# gimli1_1.net
KiCad netlist of a schematic drawn in EAGLE
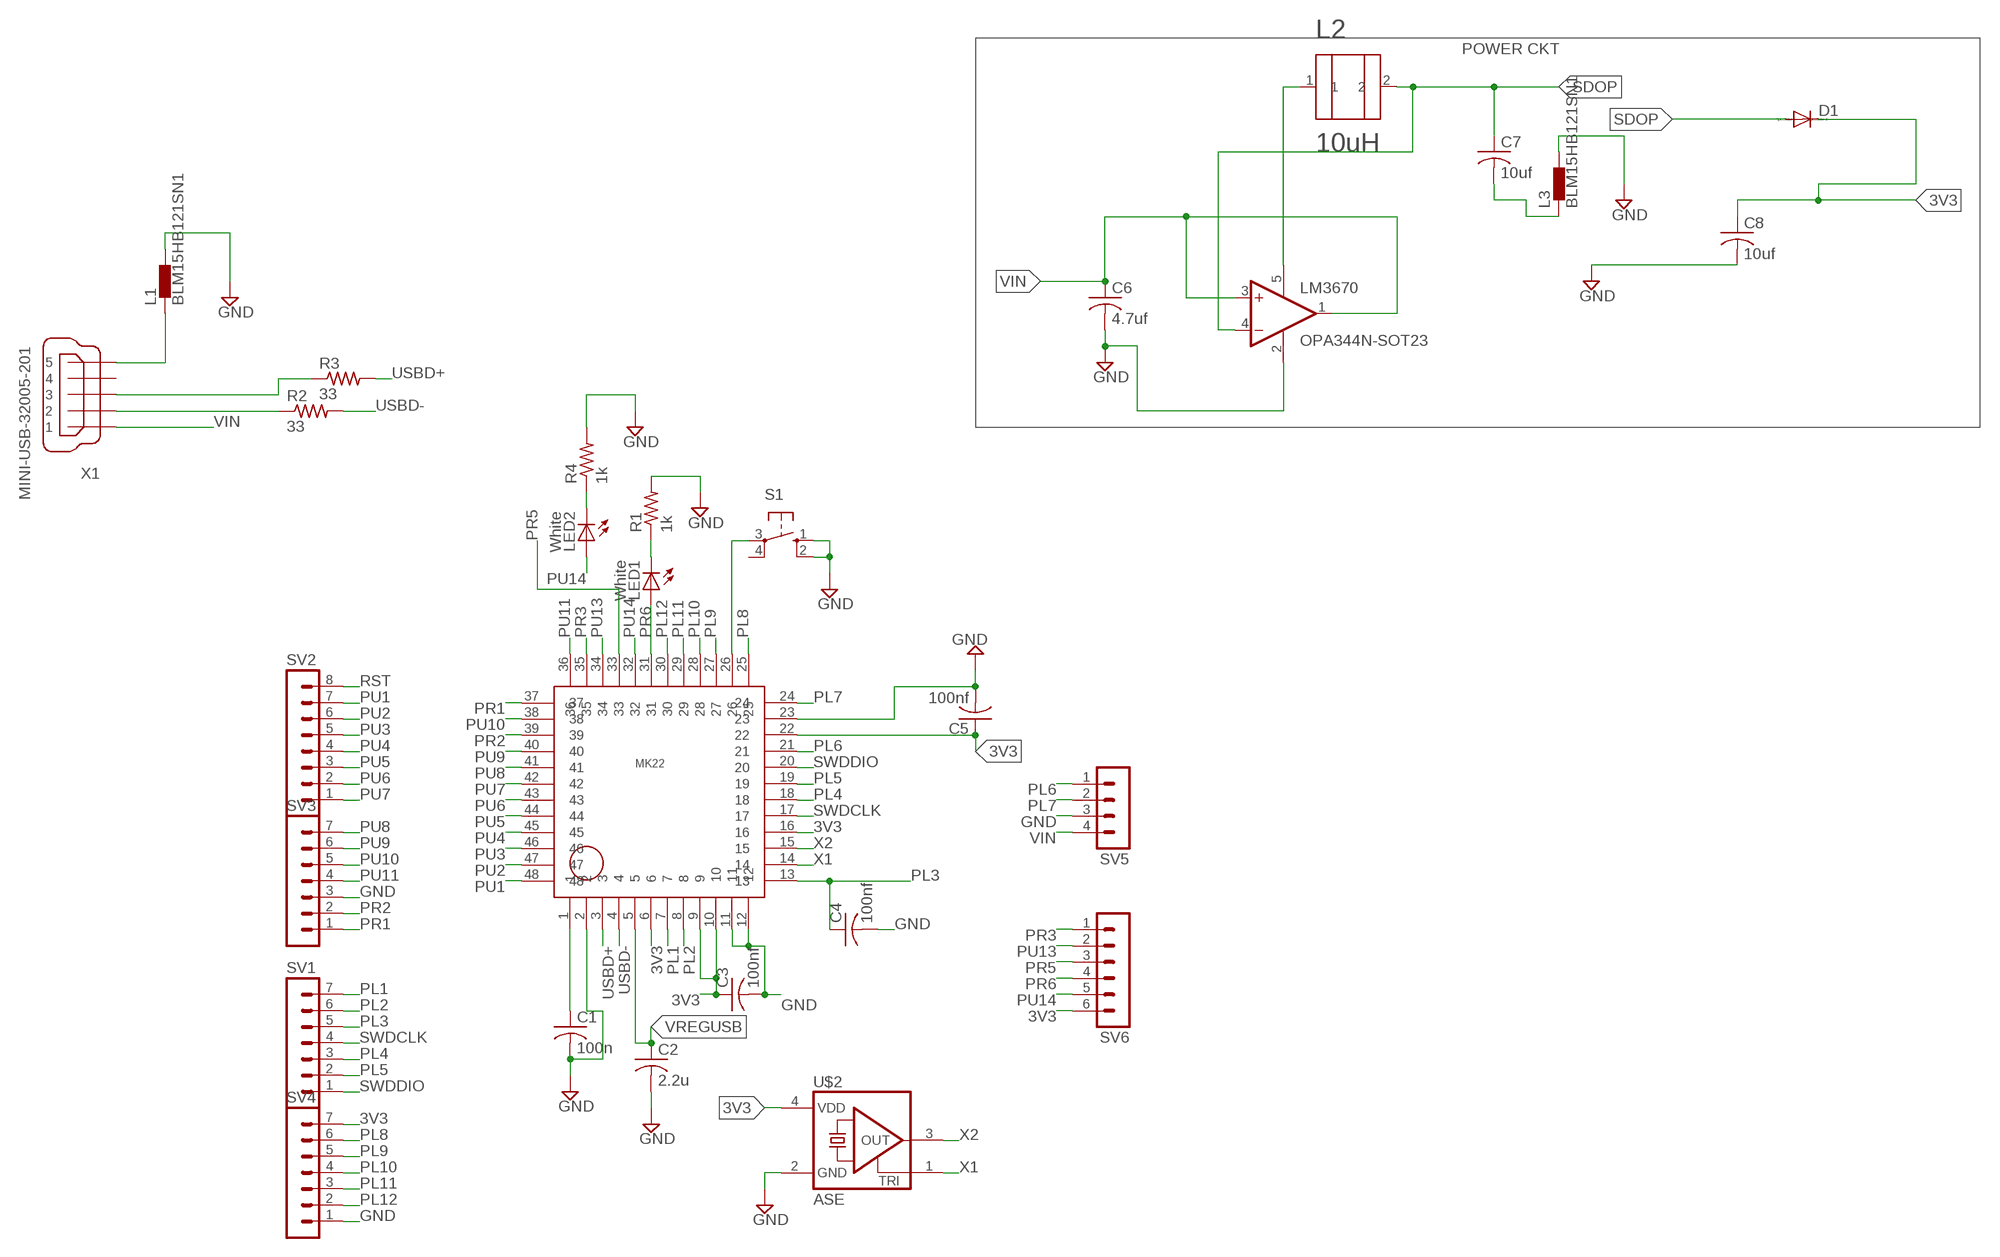
[diagram p0: schematic, sheet 1]

(export (version "E")
  (design (tool "Eeschema 10.0.6"))
  (components
    (comp (ref "C1")
      (value "100n")
      (footprint "eagle-import:C0402")
      (libsource (lib "eagle-import") (part "C-USC0402"))
    )
    (comp (ref "C2")
      (value "2.2u")
      (footprint "eagle-import:C0402")
      (libsource (lib "eagle-import") (part "C-USC0402"))
    )
    (comp (ref "C3")
      (value "100nf")
      (footprint "eagle-import:C0402")
      (libsource (lib "eagle-import") (part "C-USC0402"))
    )
    (comp (ref "C4")
      (value "100nf")
      (footprint "eagle-import:C0402")
      (libsource (lib "eagle-import") (part "C-USC0402"))
    )
    (comp (ref "C5")
      (value "100nf")
      (footprint "eagle-import:C0402")
      (libsource (lib "eagle-import") (part "C-USC0402"))
    )
    (comp (ref "C6")
      (value "4.7uf")
      (footprint "eagle-import:C0402")
      (libsource (lib "eagle-import") (part "C-USC0402"))
    )
    (comp (ref "C7")
      (value "10uf")
      (footprint "eagle-import:C0402")
      (libsource (lib "eagle-import") (part "C-USC0402"))
    )
    (comp (ref "C8")
      (value "10uf")
      (footprint "eagle-import:C0402")
      (libsource (lib "eagle-import") (part "C-USC0402"))
    )
    (comp (ref "D1")
      (value "DIODE-MICROMELF-W")
      (footprint "eagle-import:MICROMELF-W")
      (libsource (lib "eagle-import") (part "DIODE-MICROMELF-W"))
    )
    (comp (ref "L1")
      (value "BLM15HB121SN1")
      (footprint "eagle-import:0402")
      (libsource (lib "eagle-import") (part "BLM15HB121SN1"))
    )
    (comp (ref "L2")
      (value "10uH")
      (footprint "eagle-import:INDUCTNEW")
      (libsource (lib "eagle-import") (part "INDUCTNEW"))
    )
    (comp (ref "L3")
      (value "BLM15HB121SN1")
      (footprint "eagle-import:0402")
      (libsource (lib "eagle-import") (part "BLM15HB121SN1"))
    )
    (comp (ref "LED1")
      (value "White")
      (footprint "eagle-import:SML0603")
      (libsource (lib "eagle-import") (part "LEDSML0603"))
    )
    (comp (ref "LED2")
      (value "White")
      (footprint "eagle-import:SML0603")
      (libsource (lib "eagle-import") (part "LEDSML0603"))
    )
    (comp (ref "LM3670")
      (value "OPA344N-SOT23")
      (footprint "eagle-import:SOT23-5")
      (libsource (lib "eagle-import") (part "OPA-SOT23344N"))
    )
    (comp (ref "MK22")
      (value "LQFP48")
      (footprint "eagle-import:LQFP48")
      (libsource (lib "eagle-import") (part "LQFP48"))
    )
    (comp (ref "R1")
      (value "1k")
      (footprint "eagle-import:R0402")
      (libsource (lib "eagle-import") (part "R-US_R0402"))
    )
    (comp (ref "R2")
      (value "33")
      (footprint "eagle-import:R0402")
      (libsource (lib "eagle-import") (part "R-US_R0402"))
    )
    (comp (ref "R3")
      (value "33")
      (footprint "eagle-import:R0402")
      (libsource (lib "eagle-import") (part "R-US_R0402"))
    )
    (comp (ref "R4")
      (value "1k")
      (footprint "eagle-import:R0402")
      (libsource (lib "eagle-import") (part "R-US_R0402"))
    )
    (comp (ref "S1")
      (value "10-XX")
      (footprint "eagle-import:B3F-10XX")
      (fields (field (name "MPN") "B3F-1000"))
      (libsource (lib "eagle-import") (part "10-XX"))
    )
    (comp (ref "SV1")
      (value "MA07-1")
      (footprint "eagle-import:MA07-1")
      (libsource (lib "eagle-import") (part "MA07-1"))
    )
    (comp (ref "SV2")
      (value "MA08-1")
      (footprint "eagle-import:MA08-1")
      (libsource (lib "eagle-import") (part "MA08-1"))
    )
    (comp (ref "SV3")
      (value "MA07-1")
      (footprint "eagle-import:MA07-1")
      (libsource (lib "eagle-import") (part "MA07-1"))
    )
    (comp (ref "SV4")
      (value "MA07-1")
      (footprint "eagle-import:MA07-1")
      (libsource (lib "eagle-import") (part "MA07-1"))
    )
    (comp (ref "SV5")
      (value "MA04-1")
      (footprint "eagle-import:MA04-1")
      (libsource (lib "eagle-import") (part "MA04-1"))
    )
    (comp (ref "SV6")
      (value "MA06-1")
      (footprint "eagle-import:MA06-1")
      (libsource (lib "eagle-import") (part "MA06-1"))
    )
    (comp (ref "U$2")
      (value "ASE")
      (footprint "eagle-import:ASE")
      (libsource (lib "eagle-import") (part "ASE"))
    )
    (comp (ref "X1")
      (value "MINI-USB-32005-201")
      (footprint "eagle-import:32005-201")
      (libsource (lib "eagle-import") (part "MINI-USB-32005-201"))
    )
  )
  (nets
    (net (code "1") (name "/PL1") (class "Default")
      (node (ref "MK22") (pin "7") (pinfunction "7_7") (pintype "bidirectional"))
      (node (ref "SV1") (pin "7") (pinfunction "7_7") (pintype "passive"))
    )
    (net (code "2") (name "/PL2") (class "Default")
      (node (ref "MK22") (pin "8") (pinfunction "8_8") (pintype "bidirectional"))
      (node (ref "SV1") (pin "6") (pinfunction "6_6") (pintype "passive"))
    )
    (net (code "3") (name "/PL3") (class "Default")
      (node (ref "C4") (pin "1") (pinfunction "1_1") (pintype "passive"))
      (node (ref "MK22") (pin "13") (pinfunction "13_13") (pintype "bidirectional"))
      (node (ref "SV1") (pin "5") (pinfunction "5_5") (pintype "passive"))
    )
    (net (code "4") (name "/PL4") (class "Default")
      (node (ref "MK22") (pin "18") (pinfunction "18_18") (pintype "bidirectional"))
      (node (ref "SV1") (pin "3") (pinfunction "3_3") (pintype "passive"))
    )
    (net (code "5") (name "/PL5") (class "Default")
      (node (ref "MK22") (pin "19") (pinfunction "19_19") (pintype "bidirectional"))
      (node (ref "SV1") (pin "2") (pinfunction "2_2") (pintype "passive"))
    )
    (net (code "6") (name "/PL6") (class "Default")
      (node (ref "MK22") (pin "21") (pinfunction "21_21") (pintype "bidirectional"))
      (node (ref "SV5") (pin "1") (pinfunction "1_1") (pintype "passive"))
    )
    (net (code "7") (name "/PL7") (class "Default")
      (node (ref "MK22") (pin "24") (pinfunction "24_24") (pintype "bidirectional"))
      (node (ref "SV5") (pin "2") (pinfunction "2_2") (pintype "passive"))
    )
    (net (code "8") (name "/PL8") (class "Default")
      (node (ref "MK22") (pin "25") (pinfunction "25_25") (pintype "bidirectional"))
      (node (ref "SV4") (pin "6") (pinfunction "6_6") (pintype "passive"))
    )
    (net (code "9") (name "/PL9") (class "Default")
      (node (ref "MK22") (pin "27") (pinfunction "27_27") (pintype "bidirectional"))
      (node (ref "SV4") (pin "5") (pinfunction "5_5") (pintype "passive"))
    )
    (net (code "10") (name "/PL10") (class "Default")
      (node (ref "MK22") (pin "28") (pinfunction "28_28") (pintype "bidirectional"))
      (node (ref "SV4") (pin "4") (pinfunction "4_4") (pintype "passive"))
    )
    (net (code "11") (name "/PL11") (class "Default")
      (node (ref "MK22") (pin "29") (pinfunction "29_29") (pintype "bidirectional"))
      (node (ref "SV4") (pin "3") (pinfunction "3_3") (pintype "passive"))
    )
    (net (code "12") (name "/PL12") (class "Default")
      (node (ref "MK22") (pin "30") (pinfunction "30_30") (pintype "bidirectional"))
      (node (ref "SV4") (pin "2") (pinfunction "2_2") (pintype "passive"))
    )
    (net (code "13") (name "/PR1") (class "Default")
      (node (ref "MK22") (pin "37") (pinfunction "37_37") (pintype "bidirectional"))
      (node (ref "SV3") (pin "1") (pinfunction "1_1") (pintype "passive"))
    )
    (net (code "14") (name "/PR2") (class "Default")
      (node (ref "MK22") (pin "39") (pinfunction "39_39") (pintype "bidirectional"))
      (node (ref "SV3") (pin "2") (pinfunction "2_2") (pintype "passive"))
    )
    (net (code "15") (name "/PR3") (class "Default")
      (node (ref "MK22") (pin "35") (pinfunction "35_35") (pintype "bidirectional"))
      (node (ref "SV6") (pin "1") (pinfunction "1_1") (pintype "passive"))
    )
    (net (code "16") (name "/PR5") (class "Default")
      (node (ref "MK22") (pin "33") (pinfunction "33_33") (pintype "bidirectional"))
      (node (ref "SV6") (pin "3") (pinfunction "3_3") (pintype "passive"))
    )
    (net (code "17") (name "/PR6") (class "Default")
      (node (ref "LED1") (pin "A") (pinfunction "A_A") (pintype "passive"))
      (node (ref "MK22") (pin "31") (pinfunction "31_31") (pintype "bidirectional"))
      (node (ref "SV6") (pin "4") (pinfunction "4_4") (pintype "passive"))
    )
    (net (code "18") (name "/PU1") (class "Default")
      (node (ref "MK22") (pin "48") (pinfunction "48_48") (pintype "bidirectional"))
      (node (ref "SV2") (pin "7") (pinfunction "7_7") (pintype "passive"))
    )
    (net (code "19") (name "/PU2") (class "Default")
      (node (ref "MK22") (pin "47") (pinfunction "47_47") (pintype "bidirectional"))
      (node (ref "SV2") (pin "6") (pinfunction "6_6") (pintype "passive"))
    )
    (net (code "20") (name "/PU3") (class "Default")
      (node (ref "MK22") (pin "46") (pinfunction "46_46") (pintype "bidirectional"))
      (node (ref "SV2") (pin "5") (pinfunction "5_5") (pintype "passive"))
    )
    (net (code "21") (name "/PU4") (class "Default")
      (node (ref "MK22") (pin "45") (pinfunction "45_45") (pintype "bidirectional"))
      (node (ref "SV2") (pin "4") (pinfunction "4_4") (pintype "passive"))
    )
    (net (code "22") (name "/PU5") (class "Default")
      (node (ref "MK22") (pin "44") (pinfunction "44_44") (pintype "bidirectional"))
      (node (ref "SV2") (pin "3") (pinfunction "3_3") (pintype "passive"))
    )
    (net (code "23") (name "/PU6") (class "Default")
      (node (ref "MK22") (pin "43") (pinfunction "43_43") (pintype "bidirectional"))
      (node (ref "SV2") (pin "2") (pinfunction "2_2") (pintype "passive"))
    )
    (net (code "24") (name "/PU7") (class "Default")
      (node (ref "MK22") (pin "42") (pinfunction "42_42") (pintype "bidirectional"))
      (node (ref "SV2") (pin "1") (pinfunction "1_1") (pintype "passive"))
    )
    (net (code "25") (name "/PU8") (class "Default")
      (node (ref "MK22") (pin "41") (pinfunction "41_41") (pintype "bidirectional"))
      (node (ref "SV3") (pin "7") (pinfunction "7_7") (pintype "passive"))
    )
    (net (code "26") (name "/PU9") (class "Default")
      (node (ref "MK22") (pin "40") (pinfunction "40_40") (pintype "bidirectional"))
      (node (ref "SV3") (pin "6") (pinfunction "6_6") (pintype "passive"))
    )
    (net (code "27") (name "/PU10") (class "Default")
      (node (ref "MK22") (pin "38") (pinfunction "38_38") (pintype "bidirectional"))
      (node (ref "SV3") (pin "5") (pinfunction "5_5") (pintype "passive"))
    )
    (net (code "28") (name "/PU11") (class "Default")
      (node (ref "MK22") (pin "36") (pinfunction "36_36") (pintype "bidirectional"))
      (node (ref "SV3") (pin "4") (pinfunction "4_4") (pintype "passive"))
    )
    (net (code "29") (name "/PU13") (class "Default")
      (node (ref "MK22") (pin "34") (pinfunction "34_34") (pintype "bidirectional"))
      (node (ref "SV6") (pin "2") (pinfunction "2_2") (pintype "passive"))
    )
    (net (code "30") (name "/PU14") (class "Default")
      (node (ref "LED2") (pin "A") (pinfunction "A_A") (pintype "passive"))
      (node (ref "MK22") (pin "32") (pinfunction "32_32") (pintype "bidirectional"))
      (node (ref "SV6") (pin "5") (pinfunction "5_5") (pintype "passive"))
    )
    (net (code "31") (name "/RST") (class "Default")
      (node (ref "MK22") (pin "26") (pinfunction "26_26") (pintype "bidirectional"))
      (node (ref "S1") (pin "3") (pinfunction "P_3") (pintype "passive"))
      (node (ref "SV2") (pin "8") (pinfunction "8_8") (pintype "passive"))
    )
    (net (code "32") (name "/SWDCLK") (class "Default")
      (node (ref "MK22") (pin "17") (pinfunction "17_17") (pintype "bidirectional"))
      (node (ref "SV1") (pin "4") (pinfunction "4_4") (pintype "passive"))
    )
    (net (code "33") (name "/SWDDIO") (class "Default")
      (node (ref "MK22") (pin "20") (pinfunction "20_20") (pintype "bidirectional"))
      (node (ref "SV1") (pin "1") (pinfunction "1_1") (pintype "passive"))
    )
    (net (code "34") (name "/USBD+") (class "Default")
      (node (ref "MK22") (pin "3") (pinfunction "3_3") (pintype "bidirectional"))
      (node (ref "R3") (pin "2") (pinfunction "2_2") (pintype "passive"))
    )
    (net (code "35") (name "/USBD-") (class "Default")
      (node (ref "MK22") (pin "4") (pinfunction "4_4") (pintype "bidirectional"))
      (node (ref "R2") (pin "2") (pinfunction "2_2") (pintype "passive"))
    )
    (net (code "36") (name "/X1") (class "Default")
      (node (ref "MK22") (pin "14") (pinfunction "14_14") (pintype "bidirectional"))
      (node (ref "U$2") (pin "1") (pinfunction "TRI_1") (pintype "input"))
    )
    (net (code "37") (name "/X2") (class "Default")
      (node (ref "MK22") (pin "15") (pinfunction "15_15") (pintype "bidirectional"))
      (node (ref "U$2") (pin "3") (pinfunction "OUT_3") (pintype "output"))
    )
    (net (code "38") (name "3V3") (class "Default")
      (node (ref "C3") (pin "1") (pinfunction "1_1") (pintype "passive"))
      (node (ref "C5") (pin "1") (pinfunction "1_1") (pintype "passive"))
      (node (ref "C8") (pin "1") (pinfunction "1_1") (pintype "passive"))
      (node (ref "D1") (pin "C") (pinfunction "C_C") (pintype "passive"))
      (node (ref "MK22") (pin "10") (pinfunction "10_10") (pintype "bidirectional"))
      (node (ref "MK22") (pin "16") (pinfunction "16_16") (pintype "bidirectional"))
      (node (ref "MK22") (pin "22") (pinfunction "22_22") (pintype "bidirectional"))
      (node (ref "MK22") (pin "6") (pinfunction "6_6") (pintype "bidirectional"))
      (node (ref "MK22") (pin "9") (pinfunction "9_9") (pintype "bidirectional"))
      (node (ref "SV4") (pin "7") (pinfunction "7_7") (pintype "passive"))
      (node (ref "SV6") (pin "6") (pinfunction "6_6") (pintype "passive"))
      (node (ref "U$2") (pin "4") (pinfunction "VDD_4") (pintype "power_in"))
    )
    (net (code "39") (name "GND") (class "Default")
      (node (ref "C1") (pin "2") (pinfunction "2_2") (pintype "passive"))
      (node (ref "C2") (pin "2") (pinfunction "2_2") (pintype "passive"))
      (node (ref "C3") (pin "2") (pinfunction "2_2") (pintype "passive"))
      (node (ref "C4") (pin "2") (pinfunction "2_2") (pintype "passive"))
      (node (ref "C5") (pin "2") (pinfunction "2_2") (pintype "passive"))
      (node (ref "C6") (pin "2") (pinfunction "2_2") (pintype "passive"))
      (node (ref "C8") (pin "2") (pinfunction "2_2") (pintype "passive"))
      (node (ref "L1") (pin "1") (pinfunction "1_1") (pintype "passive"))
      (node (ref "L1") (pin "2") (pinfunction "2_2") (pintype "passive"))
      (node (ref "L3") (pin "2") (pinfunction "2_2") (pintype "passive"))
      (node (ref "LM3670") (pin "2") (pinfunction "V-_2") (pintype "power_in"))
      (node (ref "MK22") (pin "11") (pinfunction "11_11") (pintype "bidirectional"))
      (node (ref "MK22") (pin "12") (pinfunction "12_12") (pintype "bidirectional"))
      (node (ref "MK22") (pin "2") (pinfunction "2_2") (pintype "bidirectional"))
      (node (ref "MK22") (pin "23") (pinfunction "23_23") (pintype "bidirectional"))
      (node (ref "R1") (pin "2") (pinfunction "2_2") (pintype "passive"))
      (node (ref "R4") (pin "2") (pinfunction "2_2") (pintype "passive"))
      (node (ref "S1") (pin "1") (pinfunction "S_1") (pintype "passive"))
      (node (ref "S1") (pin "2") (pinfunction "S1_2") (pintype "passive"))
      (node (ref "SV3") (pin "3") (pinfunction "3_3") (pintype "passive"))
      (node (ref "SV4") (pin "1") (pinfunction "1_1") (pintype "passive"))
      (node (ref "SV5") (pin "3") (pinfunction "3_3") (pintype "passive"))
      (node (ref "U$2") (pin "2") (pinfunction "GND_2") (pintype "power_in"))
      (node (ref "X1") (pin "5") (pinfunction "5_5") (pintype "passive"))
    )
    (net (code "40") (name "Net-(C1-Pad1)") (class "Default")
      (node (ref "C1") (pin "1") (pinfunction "1_1") (pintype "passive"))
      (node (ref "MK22") (pin "1") (pinfunction "1_1") (pintype "bidirectional"))
    )
    (net (code "41") (name "Net-(C7-Pad2)") (class "Default")
      (node (ref "C7") (pin "2") (pinfunction "2_2") (pintype "passive"))
      (node (ref "L3") (pin "1") (pinfunction "1_1") (pintype "passive"))
    )
    (net (code "42") (name "Net-(LED1-PadC)") (class "Default")
      (node (ref "LED1") (pin "C") (pinfunction "C_C") (pintype "passive"))
      (node (ref "R1") (pin "1") (pinfunction "1_1") (pintype "passive"))
    )
    (net (code "43") (name "Net-(LED2-PadC)") (class "Default")
      (node (ref "LED2") (pin "C") (pinfunction "C_C") (pintype "passive"))
      (node (ref "R4") (pin "1") (pinfunction "1_1") (pintype "passive"))
    )
    (net (code "44") (name "Net-(LM3670-V+)") (class "Default")
      (node (ref "L2") (pin "1") (pinfunction "1_1") (pintype "bidirectional"))
      (node (ref "LM3670") (pin "5") (pinfunction "V+_5") (pintype "power_in"))
    )
    (net (code "45") (name "Net-(R2-Pad1)") (class "Default")
      (node (ref "R2") (pin "1") (pinfunction "1_1") (pintype "passive"))
      (node (ref "X1") (pin "2") (pinfunction "2_2") (pintype "passive"))
    )
    (net (code "46") (name "Net-(R3-Pad1)") (class "Default")
      (node (ref "R3") (pin "1") (pinfunction "1_1") (pintype "passive"))
      (node (ref "X1") (pin "3") (pinfunction "3_3") (pintype "passive"))
    )
    (net (code "47") (name "SDOP") (class "Default")
      (node (ref "C7") (pin "1") (pinfunction "1_1") (pintype "passive"))
      (node (ref "D1") (pin "A") (pinfunction "A_A") (pintype "passive"))
      (node (ref "L2") (pin "2") (pinfunction "2_2") (pintype "bidirectional"))
      (node (ref "LM3670") (pin "4") (pinfunction "-IN_4") (pintype "input"))
    )
    (net (code "48") (name "VIN") (class "Default")
      (node (ref "C6") (pin "1") (pinfunction "1_1") (pintype "passive"))
      (node (ref "LM3670") (pin "1") (pinfunction "OUT_1") (pintype "output"))
      (node (ref "LM3670") (pin "3") (pinfunction "+IN_3") (pintype "input"))
      (node (ref "SV5") (pin "4") (pinfunction "4_4") (pintype "passive"))
      (node (ref "X1") (pin "1") (pinfunction "1_1") (pintype "passive"))
    )
    (net (code "49") (name "VREGUSB") (class "Default")
      (node (ref "C2") (pin "1") (pinfunction "1_1") (pintype "passive"))
      (node (ref "MK22") (pin "5") (pinfunction "5_5") (pintype "bidirectional"))
    )
    (net (code "50") (name "unconnected-(S1-P1-Pad4)") (class "Default")
      (node (ref "S1") (pin "4") (pinfunction "P1_4") (pintype "passive"))
    )
    (net (code "51") (name "unconnected-(X1-Pad4)") (class "Default")
      (node (ref "X1") (pin "4") (pinfunction "4_4") (pintype "passive"))
    )
  )
)
